# LM_001.net
KiCad netlist of a schematic drawn in Altium Designer
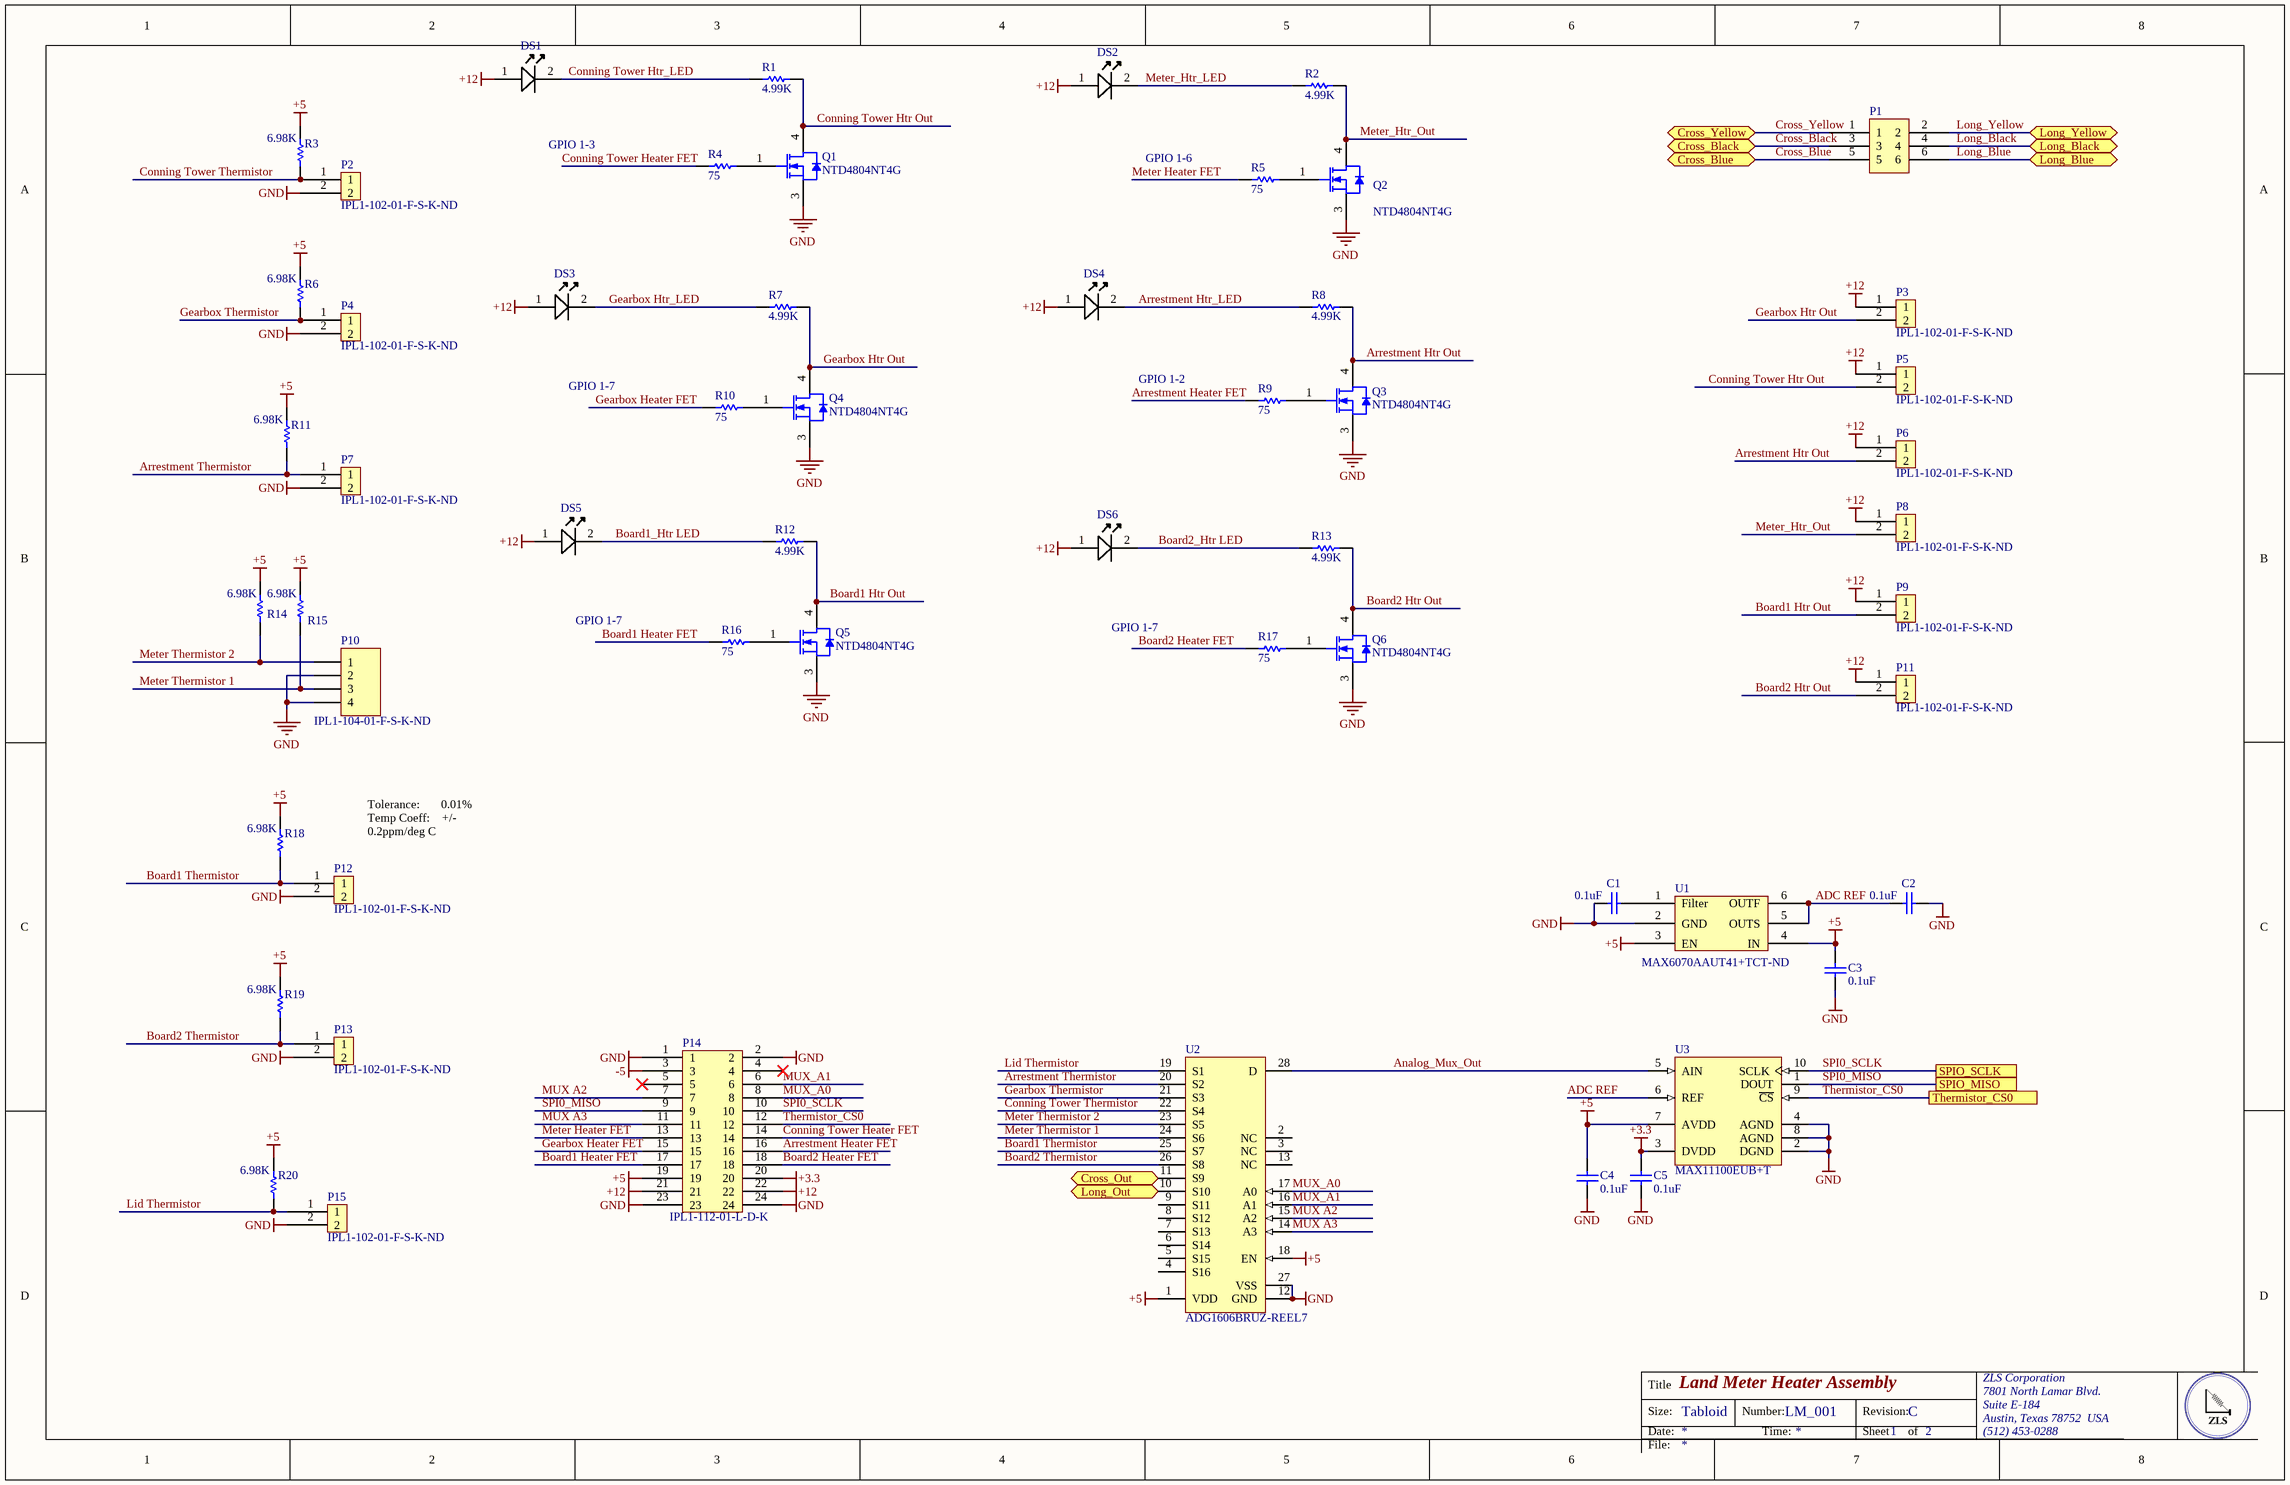
[diagram p0: LM_001.SchDoc]

(export (version "E")
  (design (tool "Eeschema 10.0.6"))
  (components
    (comp (ref "C1")
      (value "0.1uF")
      (footprint "CAPC0402(1005)60_L")
      (description "CAP CER 0.1UF 10V X7R 0402")
      (fields
        (field (name "MANUFACTURER") "Murata Electronics North America")
        (field (name "MANUFACTURER PART NUMBER") "GRM155R71A104KA01D")
      )
      (libsource (lib "Altium Content Vault") (part "CMP-1034-00252-1"))
    )
    (comp (ref "C2")
      (value "0.1uF")
      (footprint "CAPC0402(1005)60_L")
      (description "CAP CER 0.1UF 10V X7R 0402")
      (fields
        (field (name "MANUFACTURER") "Murata Electronics North America")
        (field (name "MANUFACTURER PART NUMBER") "GRM155R71A104KA01D")
      )
      (libsource (lib "Altium Content Vault") (part "CMP-1034-00252-1"))
    )
    (comp (ref "C3")
      (value "0.1uF")
      (footprint "CAPC0402(1005)60_L")
      (description "CAP CER 0.1UF 10V X7R 0402")
      (fields
        (field (name "MANUFACTURER") "Murata Electronics North America")
        (field (name "MANUFACTURER PART NUMBER") "GRM155R71A104KA01D")
      )
      (libsource (lib "Altium Content Vault") (part "CMP-1034-00252-1"))
    )
    (comp (ref "C4")
      (value "0.1uF")
      (footprint "CAPC0402(1005)60_L")
      (description "CAP CER 0.1UF 10V X7R 0402")
      (fields
        (field (name "MANUFACTURER") "Murata Electronics North America")
        (field (name "MANUFACTURER PART NUMBER") "GRM155R71A104KA01D")
      )
      (libsource (lib "Altium Content Vault") (part "CMP-1034-00252-1"))
    )
    (comp (ref "C5")
      (value "0.1uF")
      (footprint "CAPC0402(1005)60_L")
      (description "CAP CER 0.1UF 10V X7R 0402")
      (fields
        (field (name "MANUFACTURER") "Murata Electronics North America")
        (field (name "MANUFACTURER PART NUMBER") "GRM155R71A104KA01D")
      )
      (libsource (lib "Altium Content Vault") (part "CMP-1034-00252-1"))
    )
    (comp (ref "DS1")
      (value "LTST-S220KRKT")
      (footprint "0805C_L")
      (description "LED RED CLEAR CHIP SMD R/A")
      (fields (field (name "MANUFACTURER") "Vishay / Lite-On"))
      (libsource (lib "*") (part "LED A/K"))
    )
    (comp (ref "DS2")
      (value "LTST-S220KRKT")
      (footprint "0805C_L")
      (description "LED RED CLEAR CHIP SMD R/A")
      (fields (field (name "MANUFACTURER") "Vishay / Lite-On"))
      (libsource (lib "*") (part "LED A/K"))
    )
    (comp (ref "DS3")
      (value "LTST-S220KRKT")
      (footprint "0805C_L")
      (description "LED RED CLEAR CHIP SMD R/A")
      (fields (field (name "MANUFACTURER") "Vishay / Lite-On"))
      (libsource (lib "*") (part "LED A/K"))
    )
    (comp (ref "DS4")
      (value "LTST-S220KRKT")
      (footprint "0805C_L")
      (description "LED RED CLEAR CHIP SMD R/A")
      (fields (field (name "MANUFACTURER") "Vishay / Lite-On"))
      (libsource (lib "*") (part "LED A/K"))
    )
    (comp (ref "DS5")
      (value "LTST-S220KRKT")
      (footprint "0805C_L")
      (description "LED RED CLEAR CHIP SMD R/A")
      (fields (field (name "MANUFACTURER") "Vishay / Lite-On"))
      (libsource (lib "*") (part "LED A/K"))
    )
    (comp (ref "DS6")
      (value "LTST-S220KRKT")
      (footprint "0805C_L")
      (description "LED RED CLEAR CHIP SMD R/A")
      (fields (field (name "MANUFACTURER") "Vishay / Lite-On"))
      (libsource (lib "*") (part "LED A/K"))
    )
    (comp (ref "P1")
      (value "IPL1-103-01-L-D-K")
      (footprint "IPL1-103-01-F-D")
      (description ".100 TERMINAL ASSY")
      (fields (field (name "MANUFACTURER") "Samtec Inc."))
      (libsource (lib "ZLS_Schematic_lib") (part "IPL1-103-01-F-D"))
    )
    (comp (ref "P2")
      (value "IPL1-102-01-F-S-K")
      (footprint "IPL1-102-01-F-S-K")
      (description ".100 TERMINAL ASSEMBLY")
      (fields
        (field (name "SUPPLIER PART NUMBER 1") "IPL1-102-01-F-S-K-ND")
        (field (name "MANUFACTURER") "Samtec Inc.")
      )
      (libsource (lib "ZLS_Schematic_lib") (part "IPL1-102-01-F-S-K"))
    )
    (comp (ref "P3")
      (value "IPL1-102-01-F-S-K")
      (footprint "IPL1-102-01-F-S-K")
      (description ".100 TERMINAL ASSEMBLY")
      (fields
        (field (name "SUPPLIER PART NUMBER 1") "IPL1-102-01-F-S-K-ND")
        (field (name "MANUFACTURER") "Samtec Inc.")
      )
      (libsource (lib "ZLS_Schematic_lib") (part "IPL1-102-01-F-S-K"))
    )
    (comp (ref "P4")
      (value "IPL1-102-01-F-S-K")
      (footprint "IPL1-102-01-F-S-K")
      (description ".100 TERMINAL ASSEMBLY")
      (fields
        (field (name "SUPPLIER PART NUMBER 1") "IPL1-102-01-F-S-K-ND")
        (field (name "MANUFACTURER") "Samtec Inc.")
      )
      (libsource (lib "ZLS_Schematic_lib") (part "IPL1-102-01-F-S-K"))
    )
    (comp (ref "P5")
      (value "IPL1-102-01-F-S-K")
      (footprint "IPL1-102-01-F-S-K")
      (description ".100 TERMINAL ASSEMBLY")
      (fields
        (field (name "SUPPLIER PART NUMBER 1") "IPL1-102-01-F-S-K-ND")
        (field (name "MANUFACTURER") "Samtec Inc.")
      )
      (libsource (lib "ZLS_Schematic_lib") (part "IPL1-102-01-F-S-K"))
    )
    (comp (ref "P6")
      (value "IPL1-102-01-F-S-K")
      (footprint "IPL1-102-01-F-S-K")
      (description ".100 TERMINAL ASSEMBLY")
      (fields
        (field (name "SUPPLIER PART NUMBER 1") "IPL1-102-01-F-S-K-ND")
        (field (name "MANUFACTURER") "Samtec Inc.")
      )
      (libsource (lib "ZLS_Schematic_lib") (part "IPL1-102-01-F-S-K"))
    )
    (comp (ref "P7")
      (value "IPL1-102-01-F-S-K")
      (footprint "IPL1-102-01-F-S-K")
      (description ".100 TERMINAL ASSEMBLY")
      (fields
        (field (name "SUPPLIER PART NUMBER 1") "IPL1-102-01-F-S-K-ND")
        (field (name "MANUFACTURER") "Samtec Inc.")
      )
      (libsource (lib "ZLS_Schematic_lib") (part "IPL1-102-01-F-S-K"))
    )
    (comp (ref "P8")
      (value "IPL1-102-01-F-S-K")
      (footprint "IPL1-102-01-F-S-K")
      (description ".100 TERMINAL ASSEMBLY")
      (fields
        (field (name "SUPPLIER PART NUMBER 1") "IPL1-102-01-F-S-K-ND")
        (field (name "MANUFACTURER") "Samtec Inc.")
      )
      (libsource (lib "ZLS_Schematic_lib") (part "IPL1-102-01-F-S-K"))
    )
    (comp (ref "P9")
      (value "IPL1-102-01-F-S-K")
      (footprint "IPL1-102-01-F-S-K")
      (description ".100 TERMINAL ASSEMBLY")
      (fields
        (field (name "SUPPLIER PART NUMBER 1") "IPL1-102-01-F-S-K-ND")
        (field (name "MANUFACTURER") "Samtec Inc.")
      )
      (libsource (lib "ZLS_Schematic_lib") (part "IPL1-102-01-F-S-K"))
    )
    (comp (ref "P10")
      (value "IPL1-104-01-F-S-K-ND")
      (footprint "IPL1-104-01-L-S-K")
      (description ".100 TERMINAL ASSEMBLY")
      (fields
        (field (name "MANUFACTURER") "Samtec Inc.")
        (field (name "MANUFACTURER PART NUMBER") "IPL1-104-01-F-S-K")
      )
      (libsource (lib "Miscellaneous Connectors") (part "Header 4"))
    )
    (comp (ref "P11")
      (value "IPL1-102-01-F-S-K")
      (footprint "IPL1-102-01-F-S-K")
      (description ".100 TERMINAL ASSEMBLY")
      (fields
        (field (name "SUPPLIER PART NUMBER 1") "IPL1-102-01-F-S-K-ND")
        (field (name "MANUFACTURER") "Samtec Inc.")
      )
      (libsource (lib "ZLS_Schematic_lib") (part "IPL1-102-01-F-S-K"))
    )
    (comp (ref "P12")
      (value "IPL1-102-01-F-S-K")
      (footprint "IPL1-102-01-F-S-K")
      (description ".100 TERMINAL ASSEMBLY")
      (fields
        (field (name "SUPPLIER PART NUMBER 1") "IPL1-102-01-F-S-K-ND")
        (field (name "MANUFACTURER") "Samtec Inc.")
      )
      (libsource (lib "ZLS_Schematic_lib") (part "IPL1-102-01-F-S-K"))
    )
    (comp (ref "P13")
      (value "IPL1-102-01-F-S-K")
      (footprint "IPL1-102-01-F-S-K")
      (description ".100 TERMINAL ASSEMBLY")
      (fields
        (field (name "SUPPLIER PART NUMBER 1") "IPL1-102-01-F-S-K-ND")
        (field (name "MANUFACTURER") "Samtec Inc.")
      )
      (libsource (lib "ZLS_Schematic_lib") (part "IPL1-102-01-F-S-K"))
    )
    (comp (ref "P14")
      (value "IPL1-112-01-L-D-K")
      (footprint "IPL1-112-01-F-S-K")
      (fields (field (name "MANUFACTURER") "Samtec Inc."))
      (libsource (lib "ZLS_Schematic_lib") (part "IPL1-112-01-F-S-K"))
    )
    (comp (ref "P15")
      (value "IPL1-102-01-F-S-K")
      (footprint "IPL1-102-01-F-S-K")
      (description ".100 TERMINAL ASSEMBLY")
      (fields
        (field (name "SUPPLIER PART NUMBER 1") "IPL1-102-01-F-S-K-ND")
        (field (name "MANUFACTURER") "Samtec Inc.")
      )
      (libsource (lib "ZLS_Schematic_lib") (part "IPL1-102-01-F-S-K"))
    )
    (comp (ref "Q1")
      (value "NTD4804NT4G")
      (footprint "ONSC-DPAK-3-369AA-01_V")
      (description "Power MOSFET, 30 V, 117 A, Single N-Channel, 3-Pin DPAK, Pb-Free, Tape and Reel")
      (fields (field (name "MANUFACTURER") "On Semiconductor"))
      (libsource (lib "Altium Content Vault") (part "CMP-1058-00341-1"))
    )
    (comp (ref "Q2")
      (value "NTD4804NT4G")
      (footprint "ONSC-DPAK-3-369AA-01_V")
      (description "Power MOSFET, 30 V, 117 A, Single N-Channel, 3-Pin DPAK, Pb-Free, Tape and Reel")
      (fields (field (name "MANUFACTURER") "On Semiconductor"))
      (libsource (lib "Altium Content Vault") (part "CMP-1058-00341-1"))
    )
    (comp (ref "Q3")
      (value "NTD4804NT4G")
      (footprint "ONSC-DPAK-3-369AA-01_V")
      (description "Power MOSFET, 30 V, 117 A, Single N-Channel, 3-Pin DPAK, Pb-Free, Tape and Reel")
      (fields (field (name "MANUFACTURER") "On Semiconductor"))
      (libsource (lib "Altium Content Vault") (part "CMP-1058-00341-1"))
    )
    (comp (ref "Q4")
      (value "NTD4804NT4G")
      (footprint "ONSC-DPAK-3-369AA-01_V")
      (description "Power MOSFET, 30 V, 117 A, Single N-Channel, 3-Pin DPAK, Pb-Free, Tape and Reel")
      (fields (field (name "MANUFACTURER") "On Semiconductor"))
      (libsource (lib "Altium Content Vault") (part "CMP-1058-00341-1"))
    )
    (comp (ref "Q5")
      (value "NTD4804NT4G")
      (footprint "ONSC-DPAK-3-369AA-01_V")
      (description "Power MOSFET, 30 V, 117 A, Single N-Channel, 3-Pin DPAK, Pb-Free, Tape and Reel")
      (fields (field (name "MANUFACTURER") "On Semiconductor"))
      (libsource (lib "Altium Content Vault") (part "CMP-1058-00341-1"))
    )
    (comp (ref "Q6")
      (value "NTD4804NT4G")
      (footprint "ONSC-DPAK-3-369AA-01_V")
      (description "Power MOSFET, 30 V, 117 A, Single N-Channel, 3-Pin DPAK, Pb-Free, Tape and Reel")
      (fields (field (name "MANUFACTURER") "On Semiconductor"))
      (libsource (lib "Altium Content Vault") (part "CMP-1058-00341-1"))
    )
    (comp (ref "R1")
      (value "4.99K")
      (footprint "RESC0805(2012)_L")
      (description "RES SMD 4.99K OHM 1% 1/8W 0805")
      (fields
        (field (name "MANUFACTURER") "Vishay Dale")
        (field (name "MANUFACTURER PART NUMBER") "CRCW08054K99FKEA")
      )
      (libsource (lib "Altium Content Vault") (part "CMP-1013-00393-1"))
    )
    (comp (ref "R2")
      (value "4.99K")
      (footprint "RESC0805(2012)_L")
      (description "RES SMD 4.99K OHM 1% 1/8W 0805")
      (fields
        (field (name "MANUFACTURER") "Vishay Dale")
        (field (name "MANUFACTURER PART NUMBER") "CRCW08054K99FKEA")
      )
      (libsource (lib "Altium Content Vault") (part "CMP-1013-00393-1"))
    )
    (comp (ref "R3")
      (value "6.98K")
      (footprint "RESC0805(2012)_N")
      (description "RES SMD 6.98K OHM 1% 1/8W 0805")
      (fields
        (field (name "MANUFACTURER") "Vishay Dale")
        (field (name "MANUFACTURER PART NUMBER") "CRCW08056K98FKEA")
      )
      (libsource (lib "Altium Content Vault") (part "CMP-1013-00606-1"))
    )
    (comp (ref "R4")
      (value "75")
      (footprint "RESC0805(2012)_L")
      (description "RES SMD 75 OHM 1% 1/8W 0805")
      (fields
        (field (name "MANUFACTURER") "Vishay Dale")
        (field (name "MANUFACTURER PART NUMBER") "CRCW080575R0FKTA")
      )
      (libsource (lib "Altium Content Vault") (part "CMP-1013-00393-1"))
    )
    (comp (ref "R5")
      (value "75")
      (footprint "RESC0805(2012)_L")
      (description "RES SMD 75 OHM 1% 1/8W 0805")
      (fields
        (field (name "MANUFACTURER") "Vishay Dale")
        (field (name "MANUFACTURER PART NUMBER") "CRCW080575R0FKTA")
      )
      (libsource (lib "Altium Content Vault") (part "CMP-1013-00393-1"))
    )
    (comp (ref "R6")
      (value "6.98K")
      (footprint "RESC0805(2012)_N")
      (description "RES SMD 6.98K OHM 1% 1/8W 0805")
      (fields
        (field (name "MANUFACTURER") "Vishay Dale")
        (field (name "MANUFACTURER PART NUMBER") "CRCW08056K98FKEA")
      )
      (libsource (lib "Altium Content Vault") (part "CMP-1013-00606-1"))
    )
    (comp (ref "R7")
      (value "4.99K")
      (footprint "RESC0805(2012)_L")
      (description "RES SMD 4.99K OHM 1% 1/8W 0805")
      (fields
        (field (name "MANUFACTURER") "Vishay Dale")
        (field (name "MANUFACTURER PART NUMBER") "CRCW08054K99FKEA")
      )
      (libsource (lib "Altium Content Vault") (part "CMP-1013-00393-1"))
    )
    (comp (ref "R8")
      (value "4.99K")
      (footprint "RESC0805(2012)_L")
      (description "RES SMD 4.99K OHM 1% 1/8W 0805")
      (fields
        (field (name "MANUFACTURER") "Vishay Dale")
        (field (name "MANUFACTURER PART NUMBER") "CRCW08054K99FKEA")
      )
      (libsource (lib "Altium Content Vault") (part "CMP-1013-00393-1"))
    )
    (comp (ref "R9")
      (value "75")
      (footprint "RESC0805(2012)_L")
      (description "RES SMD 75 OHM 1% 1/8W 0805")
      (fields
        (field (name "MANUFACTURER") "Vishay Dale")
        (field (name "MANUFACTURER PART NUMBER") "CRCW080575R0FKTA")
      )
      (libsource (lib "Altium Content Vault") (part "CMP-1013-00393-1"))
    )
    (comp (ref "R10")
      (value "75")
      (footprint "RESC0805(2012)_L")
      (description "RES SMD 75 OHM 1% 1/8W 0805")
      (fields
        (field (name "MANUFACTURER") "Vishay Dale")
        (field (name "MANUFACTURER PART NUMBER") "CRCW080575R0FKTA")
      )
      (libsource (lib "Altium Content Vault") (part "CMP-1013-00393-1"))
    )
    (comp (ref "R11")
      (value "6.98K")
      (footprint "RESC0805(2012)_N")
      (description "RES SMD 6.98K OHM 1% 1/8W 0805")
      (fields
        (field (name "MANUFACTURER") "Vishay Dale")
        (field (name "MANUFACTURER PART NUMBER") "CRCW08056K98FKEA")
      )
      (libsource (lib "Altium Content Vault") (part "CMP-1013-00606-1"))
    )
    (comp (ref "R12")
      (value "4.99K")
      (footprint "RESC0805(2012)_L")
      (description "RES SMD 4.99K OHM 1% 1/8W 0805")
      (fields
        (field (name "MANUFACTURER") "Vishay Dale")
        (field (name "MANUFACTURER PART NUMBER") "CRCW08054K99FKEA")
      )
      (libsource (lib "Altium Content Vault") (part "CMP-1013-00393-1"))
    )
    (comp (ref "R13")
      (value "4.99K")
      (footprint "RESC0805(2012)_L")
      (description "RES SMD 4.99K OHM 1% 1/8W 0805")
      (fields
        (field (name "MANUFACTURER") "Vishay Dale")
        (field (name "MANUFACTURER PART NUMBER") "CRCW08054K99FKEA")
      )
      (libsource (lib "Altium Content Vault") (part "CMP-1013-00393-1"))
    )
    (comp (ref "R14")
      (value "6.98K")
      (footprint "RESC0805(2012)_N")
      (description "RES SMD 6.98K OHM 1% 1/8W 0805")
      (fields
        (field (name "MANUFACTURER") "Vishay Dale")
        (field (name "MANUFACTURER PART NUMBER") "CRCW08056K98FKEA")
      )
      (libsource (lib "Altium Content Vault") (part "CMP-1013-00606-1"))
    )
    (comp (ref "R15")
      (value "6.98K")
      (footprint "RESC0805(2012)_N")
      (description "RES SMD 6.98K OHM 1% 1/8W 0805")
      (fields
        (field (name "MANUFACTURER") "Vishay Dale")
        (field (name "MANUFACTURER PART NUMBER") "CRCW08056K98FKEA")
      )
      (libsource (lib "Altium Content Vault") (part "CMP-1013-00606-1"))
    )
    (comp (ref "R16")
      (value "75")
      (footprint "RESC0805(2012)_L")
      (description "RES SMD 75 OHM 1% 1/8W 0805")
      (fields
        (field (name "MANUFACTURER") "Vishay Dale")
        (field (name "MANUFACTURER PART NUMBER") "CRCW080575R0FKTA")
      )
      (libsource (lib "Altium Content Vault") (part "CMP-1013-00393-1"))
    )
    (comp (ref "R17")
      (value "75")
      (footprint "RESC0805(2012)_L")
      (description "RES SMD 75 OHM 1% 1/8W 0805")
      (fields
        (field (name "MANUFACTURER") "Vishay Dale")
        (field (name "MANUFACTURER PART NUMBER") "CRCW080575R0FKTA")
      )
      (libsource (lib "Altium Content Vault") (part "CMP-1013-00393-1"))
    )
    (comp (ref "R18")
      (value "6.98K")
      (footprint "RESC0805(2012)_N")
      (description "RES SMD 6.98K OHM 1% 1/8W 0805")
      (fields
        (field (name "MANUFACTURER") "Vishay Dale")
        (field (name "MANUFACTURER PART NUMBER") "CRCW08056K98FKEA")
      )
      (libsource (lib "Altium Content Vault") (part "CMP-1013-00606-1"))
    )
    (comp (ref "R19")
      (value "6.98K")
      (footprint "RESC0805(2012)_N")
      (description "RES SMD 6.98K OHM 1% 1/8W 0805")
      (fields
        (field (name "MANUFACTURER") "Vishay Dale")
        (field (name "MANUFACTURER PART NUMBER") "CRCW08056K98FKEA")
      )
      (libsource (lib "Altium Content Vault") (part "CMP-1013-00606-1"))
    )
    (comp (ref "R20")
      (value "6.98K")
      (footprint "RESC0805(2012)_N")
      (description "RES SMD 6.98K OHM 1% 1/8W 0805")
      (fields
        (field (name "MANUFACTURER") "Vishay Dale")
        (field (name "MANUFACTURER PART NUMBER") "CRCW08056K98FKEA")
      )
      (libsource (lib "Altium Content Vault") (part "CMP-1013-00606-1"))
    )
    (comp (ref "U1")
      (value "MAX6070AAUT41+T")
      (footprint "SOT95P280X445-6N")
      (description "IC VREF SERIES 4.096V SOT23")
      (fields
        (field (name "SUPPLIER PART NUMBER 1") "MAX6070AAUT41+TCT-ND")
        (field (name "MANUFACTURER") "Maxim Integrated")
        (field (name "TOLERANCE") "±0.04%")
      )
      (libsource (lib "ZLS_Schematic_lib") (part "MAX6070AAUT41+T"))
    )
    (comp (ref "U2")
      (value "ADG1606BRUZ-REEL7")
      (footprint "ADI-RU-28_M")
      (description "4.5 Ohm Ron, 16-Channel, +/-5 V,+12 V,+5 V and +3.3 V Multiplexer, 28-pin SOP (RU-28), Reel")
      (fields (field (name "MANUFACTURER") "Analog Devices"))
      (libsource (lib "Altium Content Vault") (part "ADI-ADG1606-RU-28"))
    )
    (comp (ref "U3")
      (value "MAX11100EUB+T")
      (footprint "U10+2_L")
      (description "16-Bit, +5V, 200ksps ADC with 10uA Shutdown, 10-Pin uMAX, -40°C to +85°C, Pb-Free, Tape and Reel")
      (libsource (lib "Altium Content Vault") (part "CON-ADC-MAX11100-IL10"))
    )
  )
  (nets
    (net (code "1") (name "+3.3") (class "Default")
      (node (ref "C5") (pin "1") (pinfunction "1_1") (pintype "passive"))
      (node (ref "P14") (pin "20") (pinfunction "20_20") (pintype "passive"))
      (node (ref "U3") (pin "3") (pinfunction "DVDD_3") (pintype "power_in"))
    )
    (net (code "2") (name "+5") (class "Default")
      (node (ref "C3") (pin "1") (pinfunction "1_1") (pintype "passive"))
      (node (ref "C4") (pin "1") (pinfunction "1_1") (pintype "passive"))
      (node (ref "P14") (pin "19") (pinfunction "19_19") (pintype "passive"))
      (node (ref "R11") (pin "2") (pinfunction "2_2") (pintype "passive"))
      (node (ref "R14") (pin "2") (pinfunction "2_2") (pintype "passive"))
      (node (ref "R15") (pin "2") (pinfunction "2_2") (pintype "passive"))
      (node (ref "R18") (pin "2") (pinfunction "2_2") (pintype "passive"))
      (node (ref "R19") (pin "2") (pinfunction "2_2") (pintype "passive"))
      (node (ref "R20") (pin "2") (pinfunction "2_2") (pintype "passive"))
      (node (ref "R3") (pin "2") (pinfunction "2_2") (pintype "passive"))
      (node (ref "R6") (pin "2") (pinfunction "2_2") (pintype "passive"))
      (node (ref "U1") (pin "3") (pinfunction "EN_3") (pintype "passive"))
      (node (ref "U1") (pin "4") (pinfunction "IN_4") (pintype "passive"))
      (node (ref "U2") (pin "1") (pinfunction "VDD_1") (pintype "power_in"))
      (node (ref "U2") (pin "18") (pinfunction "EN_18") (pintype "input"))
      (node (ref "U3") (pin "7") (pinfunction "AVDD_7") (pintype "power_in"))
    )
    (net (code "3") (name "+12") (class "Default")
      (node (ref "DS1") (pin "1") (pinfunction "A_1") (pintype "passive"))
      (node (ref "DS2") (pin "1") (pinfunction "A_1") (pintype "passive"))
      (node (ref "DS3") (pin "1") (pinfunction "A_1") (pintype "passive"))
      (node (ref "DS4") (pin "1") (pinfunction "A_1") (pintype "passive"))
      (node (ref "DS5") (pin "1") (pinfunction "A_1") (pintype "passive"))
      (node (ref "DS6") (pin "1") (pinfunction "A_1") (pintype "passive"))
      (node (ref "P11") (pin "1") (pinfunction "1_1") (pintype "passive"))
      (node (ref "P14") (pin "21") (pinfunction "21_21") (pintype "passive"))
      (node (ref "P14") (pin "22") (pinfunction "22_22") (pintype "passive"))
      (node (ref "P3") (pin "1") (pinfunction "1_1") (pintype "passive"))
      (node (ref "P5") (pin "1") (pinfunction "1_1") (pintype "passive"))
      (node (ref "P6") (pin "1") (pinfunction "1_1") (pintype "passive"))
      (node (ref "P8") (pin "1") (pinfunction "1_1") (pintype "passive"))
      (node (ref "P9") (pin "1") (pinfunction "1_1") (pintype "passive"))
    )
    (net (code "4") (name "-5") (class "Default")
      (node (ref "P14") (pin "3") (pinfunction "3_3") (pintype "passive"))
    )
    (net (code "5") (name "/ADC REF") (class "Default")
      (node (ref "C2") (pin "2") (pinfunction "2_2") (pintype "passive"))
      (node (ref "U1") (pin "5") (pinfunction "OUTS_5") (pintype "passive"))
      (node (ref "U1") (pin "6") (pinfunction "OUTF_6") (pintype "passive"))
      (node (ref "U3") (pin "6") (pinfunction "REF_6") (pintype "input"))
    )
    (net (code "6") (name "/Analog_Mux_Out") (class "Default")
      (node (ref "U2") (pin "28") (pinfunction "D_28") (pintype "passive"))
      (node (ref "U3") (pin "5") (pinfunction "AIN_5") (pintype "input"))
    )
    (net (code "7") (name "/Arrestment Heater FET") (class "Default")
      (node (ref "P14") (pin "16") (pinfunction "16_16") (pintype "passive"))
      (node (ref "R9") (pin "1") (pinfunction "1_1") (pintype "passive"))
    )
    (net (code "8") (name "/Arrestment Htr Out") (class "Default")
      (node (ref "P6") (pin "2") (pinfunction "2_2") (pintype "passive"))
      (node (ref "Q3") (pin "4") (pinfunction "D_4") (pintype "passive"))
      (node (ref "R8") (pin "1") (pinfunction "1_1") (pintype "passive"))
    )
    (net (code "9") (name "/Arrestment Htr_LED") (class "Default")
      (node (ref "DS4") (pin "2") (pinfunction "K_2") (pintype "passive"))
      (node (ref "R8") (pin "2") (pinfunction "2_2") (pintype "passive"))
    )
    (net (code "10") (name "/Arrestment Thermistor") (class "Default")
      (node (ref "P7") (pin "1") (pinfunction "1_1") (pintype "passive"))
      (node (ref "R11") (pin "1") (pinfunction "1_1") (pintype "passive"))
      (node (ref "U2") (pin "20") (pinfunction "S2_20") (pintype "passive"))
    )
    (net (code "11") (name "/Board1 Heater FET") (class "Default")
      (node (ref "P14") (pin "17") (pinfunction "17_17") (pintype "passive"))
      (node (ref "R16") (pin "1") (pinfunction "1_1") (pintype "passive"))
    )
    (net (code "12") (name "/Board1 Htr Out") (class "Default")
      (node (ref "P9") (pin "2") (pinfunction "2_2") (pintype "passive"))
      (node (ref "Q5") (pin "4") (pinfunction "D_4") (pintype "passive"))
      (node (ref "R12") (pin "1") (pinfunction "1_1") (pintype "passive"))
    )
    (net (code "13") (name "/Board1 Thermistor") (class "Default")
      (node (ref "P12") (pin "1") (pinfunction "1_1") (pintype "passive"))
      (node (ref "R18") (pin "1") (pinfunction "1_1") (pintype "passive"))
      (node (ref "U2") (pin "25") (pinfunction "S7_25") (pintype "passive"))
    )
    (net (code "14") (name "/Board1_Htr LED") (class "Default")
      (node (ref "DS5") (pin "2") (pinfunction "K_2") (pintype "passive"))
      (node (ref "R12") (pin "2") (pinfunction "2_2") (pintype "passive"))
    )
    (net (code "15") (name "/Board2 Heater FET") (class "Default")
      (node (ref "P14") (pin "18") (pinfunction "18_18") (pintype "passive"))
      (node (ref "R17") (pin "1") (pinfunction "1_1") (pintype "passive"))
    )
    (net (code "16") (name "/Board2 Htr Out") (class "Default")
      (node (ref "P11") (pin "2") (pinfunction "2_2") (pintype "passive"))
      (node (ref "Q6") (pin "4") (pinfunction "D_4") (pintype "passive"))
      (node (ref "R13") (pin "1") (pinfunction "1_1") (pintype "passive"))
    )
    (net (code "17") (name "/Board2 Thermistor") (class "Default")
      (node (ref "P13") (pin "1") (pinfunction "1_1") (pintype "passive"))
      (node (ref "R19") (pin "1") (pinfunction "1_1") (pintype "passive"))
      (node (ref "U2") (pin "26") (pinfunction "S8_26") (pintype "passive"))
    )
    (net (code "18") (name "/Board2_Htr LED") (class "Default")
      (node (ref "DS6") (pin "2") (pinfunction "K_2") (pintype "passive"))
      (node (ref "R13") (pin "2") (pinfunction "2_2") (pintype "passive"))
    )
    (net (code "19") (name "/Conning Tower Heater FET") (class "Default")
      (node (ref "P14") (pin "14") (pinfunction "14_14") (pintype "passive"))
      (node (ref "R4") (pin "1") (pinfunction "1_1") (pintype "passive"))
    )
    (net (code "20") (name "/Conning Tower Htr Out") (class "Default")
      (node (ref "P5") (pin "2") (pinfunction "2_2") (pintype "passive"))
      (node (ref "Q1") (pin "4") (pinfunction "D_4") (pintype "passive"))
      (node (ref "R1") (pin "1") (pinfunction "1_1") (pintype "passive"))
    )
    (net (code "21") (name "/Conning Tower Htr_LED") (class "Default")
      (node (ref "DS1") (pin "2") (pinfunction "K_2") (pintype "passive"))
      (node (ref "R1") (pin "2") (pinfunction "2_2") (pintype "passive"))
    )
    (net (code "22") (name "/Conning Tower Thermistor") (class "Default")
      (node (ref "P2") (pin "1") (pinfunction "1_1") (pintype "passive"))
      (node (ref "R3") (pin "1") (pinfunction "1_1") (pintype "passive"))
      (node (ref "U2") (pin "22") (pinfunction "S4_22") (pintype "passive"))
    )
    (net (code "23") (name "/Cross_Black") (class "Default")
      (node (ref "P1") (pin "3") (pinfunction "3_3") (pintype "passive"))
    )
    (net (code "24") (name "/Cross_Blue") (class "Default")
      (node (ref "P1") (pin "5") (pinfunction "5_5") (pintype "passive"))
    )
    (net (code "25") (name "/Cross_Out") (class "Default")
      (node (ref "U2") (pin "11") (pinfunction "S9_11") (pintype "passive"))
    )
    (net (code "26") (name "/Cross_Yellow") (class "Default")
      (node (ref "P1") (pin "1") (pinfunction "1_1") (pintype "passive"))
    )
    (net (code "27") (name "/Gearbox Heater FET") (class "Default")
      (node (ref "P14") (pin "15") (pinfunction "15_15") (pintype "passive"))
      (node (ref "R10") (pin "1") (pinfunction "1_1") (pintype "passive"))
    )
    (net (code "28") (name "/Gearbox Htr Out") (class "Default")
      (node (ref "P3") (pin "2") (pinfunction "2_2") (pintype "passive"))
      (node (ref "Q4") (pin "4") (pinfunction "D_4") (pintype "passive"))
      (node (ref "R7") (pin "1") (pinfunction "1_1") (pintype "passive"))
    )
    (net (code "29") (name "/Gearbox Htr_LED") (class "Default")
      (node (ref "DS3") (pin "2") (pinfunction "K_2") (pintype "passive"))
      (node (ref "R7") (pin "2") (pinfunction "2_2") (pintype "passive"))
    )
    (net (code "30") (name "/Gearbox Thermistor") (class "Default")
      (node (ref "P4") (pin "1") (pinfunction "1_1") (pintype "passive"))
      (node (ref "R6") (pin "1") (pinfunction "1_1") (pintype "passive"))
      (node (ref "U2") (pin "21") (pinfunction "S3_21") (pintype "passive"))
    )
    (net (code "31") (name "/Lid Thermistor") (class "Default")
      (node (ref "P15") (pin "1") (pinfunction "1_1") (pintype "passive"))
      (node (ref "R20") (pin "1") (pinfunction "1_1") (pintype "passive"))
      (node (ref "U2") (pin "19") (pinfunction "S1_19") (pintype "passive"))
    )
    (net (code "32") (name "/Long_Black") (class "Default")
      (node (ref "P1") (pin "4") (pinfunction "4_4") (pintype "passive"))
    )
    (net (code "33") (name "/Long_Blue") (class "Default")
      (node (ref "P1") (pin "6") (pinfunction "6_6") (pintype "passive"))
    )
    (net (code "34") (name "/Long_Out") (class "Default")
      (node (ref "U2") (pin "10") (pinfunction "S10_10") (pintype "passive"))
    )
    (net (code "35") (name "/Long_Yellow") (class "Default")
      (node (ref "P1") (pin "2") (pinfunction "2_2") (pintype "passive"))
    )
    (net (code "36") (name "/MUX A2") (class "Default")
      (node (ref "P14") (pin "7") (pinfunction "7_7") (pintype "passive"))
      (node (ref "U2") (pin "15") (pinfunction "A2_15") (pintype "input"))
    )
    (net (code "37") (name "/MUX A3") (class "Default")
      (node (ref "P14") (pin "11") (pinfunction "11_11") (pintype "passive"))
      (node (ref "U2") (pin "14") (pinfunction "A3_14") (pintype "input"))
    )
    (net (code "38") (name "/MUX_A0") (class "Default")
      (node (ref "P14") (pin "8") (pinfunction "8_8") (pintype "passive"))
      (node (ref "U2") (pin "17") (pinfunction "A0_17") (pintype "input"))
    )
    (net (code "39") (name "/MUX_A1") (class "Default")
      (node (ref "P14") (pin "6") (pinfunction "6_6") (pintype "passive"))
      (node (ref "U2") (pin "16") (pinfunction "A1_16") (pintype "input"))
    )
    (net (code "40") (name "/Meter Heater FET") (class "Default")
      (node (ref "P14") (pin "13") (pinfunction "13_13") (pintype "passive"))
      (node (ref "R5") (pin "1") (pinfunction "1_1") (pintype "passive"))
    )
    (net (code "41") (name "/Meter Thermistor 1") (class "Default")
      (node (ref "P10") (pin "3") (pinfunction "3_3") (pintype "passive"))
      (node (ref "R15") (pin "1") (pinfunction "1_1") (pintype "passive"))
      (node (ref "U2") (pin "24") (pinfunction "S6_24") (pintype "passive"))
    )
    (net (code "42") (name "/Meter Thermistor 2") (class "Default")
      (node (ref "P10") (pin "1") (pinfunction "1_1") (pintype "passive"))
      (node (ref "R14") (pin "1") (pinfunction "1_1") (pintype "passive"))
      (node (ref "U2") (pin "23") (pinfunction "S5_23") (pintype "passive"))
    )
    (net (code "43") (name "/Meter_Htr_LED") (class "Default")
      (node (ref "DS2") (pin "2") (pinfunction "K_2") (pintype "passive"))
      (node (ref "R2") (pin "2") (pinfunction "2_2") (pintype "passive"))
    )
    (net (code "44") (name "/Meter_Htr_Out") (class "Default")
      (node (ref "P8") (pin "2") (pinfunction "2_2") (pintype "passive"))
      (node (ref "Q2") (pin "4") (pinfunction "D_4") (pintype "passive"))
      (node (ref "R2") (pin "1") (pinfunction "1_1") (pintype "passive"))
    )
    (net (code "45") (name "/SPI0_MISO") (class "Default")
      (node (ref "P14") (pin "9") (pinfunction "9_9") (pintype "passive"))
      (node (ref "U3") (pin "1") (pinfunction "DOUT_1") (pintype "tri_state"))
    )
    (net (code "46") (name "/SPI0_SCLK") (class "Default")
      (node (ref "P14") (pin "10") (pinfunction "10_10") (pintype "passive"))
      (node (ref "U3") (pin "10") (pinfunction "SCLK_10") (pintype "input"))
    )
    (net (code "47") (name "/Thermistor_CS0") (class "Default")
      (node (ref "P14") (pin "12") (pinfunction "12_12") (pintype "passive"))
      (node (ref "U3") (pin "9") (pinfunction "~{CS}_9") (pintype "input"))
    )
    (net (code "48") (name "GND") (class "Default")
      (node (ref "C1") (pin "2") (pinfunction "2_2") (pintype "passive"))
      (node (ref "C2") (pin "1") (pinfunction "1_1") (pintype "passive"))
      (node (ref "C3") (pin "2") (pinfunction "2_2") (pintype "passive"))
      (node (ref "C4") (pin "2") (pinfunction "2_2") (pintype "passive"))
      (node (ref "C5") (pin "2") (pinfunction "2_2") (pintype "passive"))
      (node (ref "P10") (pin "2") (pinfunction "2_2") (pintype "passive"))
      (node (ref "P10") (pin "4") (pinfunction "4_4") (pintype "passive"))
      (node (ref "P12") (pin "2") (pinfunction "2_2") (pintype "passive"))
      (node (ref "P13") (pin "2") (pinfunction "2_2") (pintype "passive"))
      (node (ref "P14") (pin "1") (pinfunction "1_1") (pintype "passive"))
      (node (ref "P14") (pin "2") (pinfunction "2_2") (pintype "passive"))
      (node (ref "P14") (pin "23") (pinfunction "23_23") (pintype "passive"))
      (node (ref "P14") (pin "24") (pinfunction "24_24") (pintype "passive"))
      (node (ref "P15") (pin "2") (pinfunction "2_2") (pintype "passive"))
      (node (ref "P2") (pin "2") (pinfunction "2_2") (pintype "passive"))
      (node (ref "P4") (pin "2") (pinfunction "2_2") (pintype "passive"))
      (node (ref "P7") (pin "2") (pinfunction "2_2") (pintype "passive"))
      (node (ref "Q1") (pin "3") (pinfunction "S_3") (pintype "passive"))
      (node (ref "Q2") (pin "3") (pinfunction "S_3") (pintype "passive"))
      (node (ref "Q3") (pin "3") (pinfunction "S_3") (pintype "passive"))
      (node (ref "Q4") (pin "3") (pinfunction "S_3") (pintype "passive"))
      (node (ref "Q5") (pin "3") (pinfunction "S_3") (pintype "passive"))
      (node (ref "Q6") (pin "3") (pinfunction "S_3") (pintype "passive"))
      (node (ref "U1") (pin "2") (pinfunction "GND_2") (pintype "passive"))
      (node (ref "U2") (pin "12") (pinfunction "GND_12") (pintype "power_in"))
      (node (ref "U2") (pin "27") (pinfunction "VSS_27") (pintype "power_in"))
      (node (ref "U3") (pin "2") (pinfunction "DGND_2") (pintype "power_in"))
      (node (ref "U3") (pin "4") (pinfunction "AGND_4") (pintype "power_in"))
      (node (ref "U3") (pin "8") (pinfunction "AGND_8") (pintype "power_in"))
    )
    (net (code "49") (name "Net-(Q1-G)") (class "Default")
      (node (ref "Q1") (pin "1") (pinfunction "G_1") (pintype "passive"))
      (node (ref "R4") (pin "2") (pinfunction "2_2") (pintype "passive"))
    )
    (net (code "50") (name "Net-(Q2-G)") (class "Default")
      (node (ref "Q2") (pin "1") (pinfunction "G_1") (pintype "passive"))
      (node (ref "R5") (pin "2") (pinfunction "2_2") (pintype "passive"))
    )
    (net (code "51") (name "Net-(Q3-G)") (class "Default")
      (node (ref "Q3") (pin "1") (pinfunction "G_1") (pintype "passive"))
      (node (ref "R9") (pin "2") (pinfunction "2_2") (pintype "passive"))
    )
    (net (code "52") (name "Net-(Q4-G)") (class "Default")
      (node (ref "Q4") (pin "1") (pinfunction "G_1") (pintype "passive"))
      (node (ref "R10") (pin "2") (pinfunction "2_2") (pintype "passive"))
    )
    (net (code "53") (name "Net-(Q5-G)") (class "Default")
      (node (ref "Q5") (pin "1") (pinfunction "G_1") (pintype "passive"))
      (node (ref "R16") (pin "2") (pinfunction "2_2") (pintype "passive"))
    )
    (net (code "54") (name "Net-(Q6-G)") (class "Default")
      (node (ref "Q6") (pin "1") (pinfunction "G_1") (pintype "passive"))
      (node (ref "R17") (pin "2") (pinfunction "2_2") (pintype "passive"))
    )
    (net (code "55") (name "Net-(U1-Filter)") (class "Default")
      (node (ref "C1") (pin "1") (pinfunction "1_1") (pintype "passive"))
      (node (ref "U1") (pin "1") (pinfunction "Filter_1") (pintype "passive"))
    )
    (net (code "56") (name "unconnected-(P14-Pad4)") (class "Default")
      (node (ref "P14") (pin "4") (pinfunction "4_4") (pintype "passive+no_connect"))
    )
    (net (code "57") (name "unconnected-(P14-Pad5)") (class "Default")
      (node (ref "P14") (pin "5") (pinfunction "5_5") (pintype "passive+no_connect"))
    )
    (net (code "58") (name "unconnected-(U2-NC-Pad2)") (class "Default")
      (node (ref "U2") (pin "2") (pinfunction "NC_2") (pintype "passive"))
    )
    (net (code "59") (name "unconnected-(U2-NC-Pad3)") (class "Default")
      (node (ref "U2") (pin "3") (pinfunction "NC_3") (pintype "passive"))
    )
    (net (code "60") (name "unconnected-(U2-NC-Pad13)") (class "Default")
      (node (ref "U2") (pin "13") (pinfunction "NC_13") (pintype "passive"))
    )
    (net (code "61") (name "unconnected-(U2-S11-Pad9)") (class "Default")
      (node (ref "U2") (pin "9") (pinfunction "S11_9") (pintype "passive"))
    )
    (net (code "62") (name "unconnected-(U2-S12-Pad8)") (class "Default")
      (node (ref "U2") (pin "8") (pinfunction "S12_8") (pintype "passive"))
    )
    (net (code "63") (name "unconnected-(U2-S13-Pad7)") (class "Default")
      (node (ref "U2") (pin "7") (pinfunction "S13_7") (pintype "passive"))
    )
    (net (code "64") (name "unconnected-(U2-S14-Pad6)") (class "Default")
      (node (ref "U2") (pin "6") (pinfunction "S14_6") (pintype "passive"))
    )
    (net (code "65") (name "unconnected-(U2-S15-Pad5)") (class "Default")
      (node (ref "U2") (pin "5") (pinfunction "S15_5") (pintype "passive"))
    )
    (net (code "66") (name "unconnected-(U2-S16-Pad4)") (class "Default")
      (node (ref "U2") (pin "4") (pinfunction "S16_4") (pintype "passive"))
    )
  )
)
